# Fri3D_2026_ESP32.net
KiCad netlist of a schematic drawn in Altium Designer
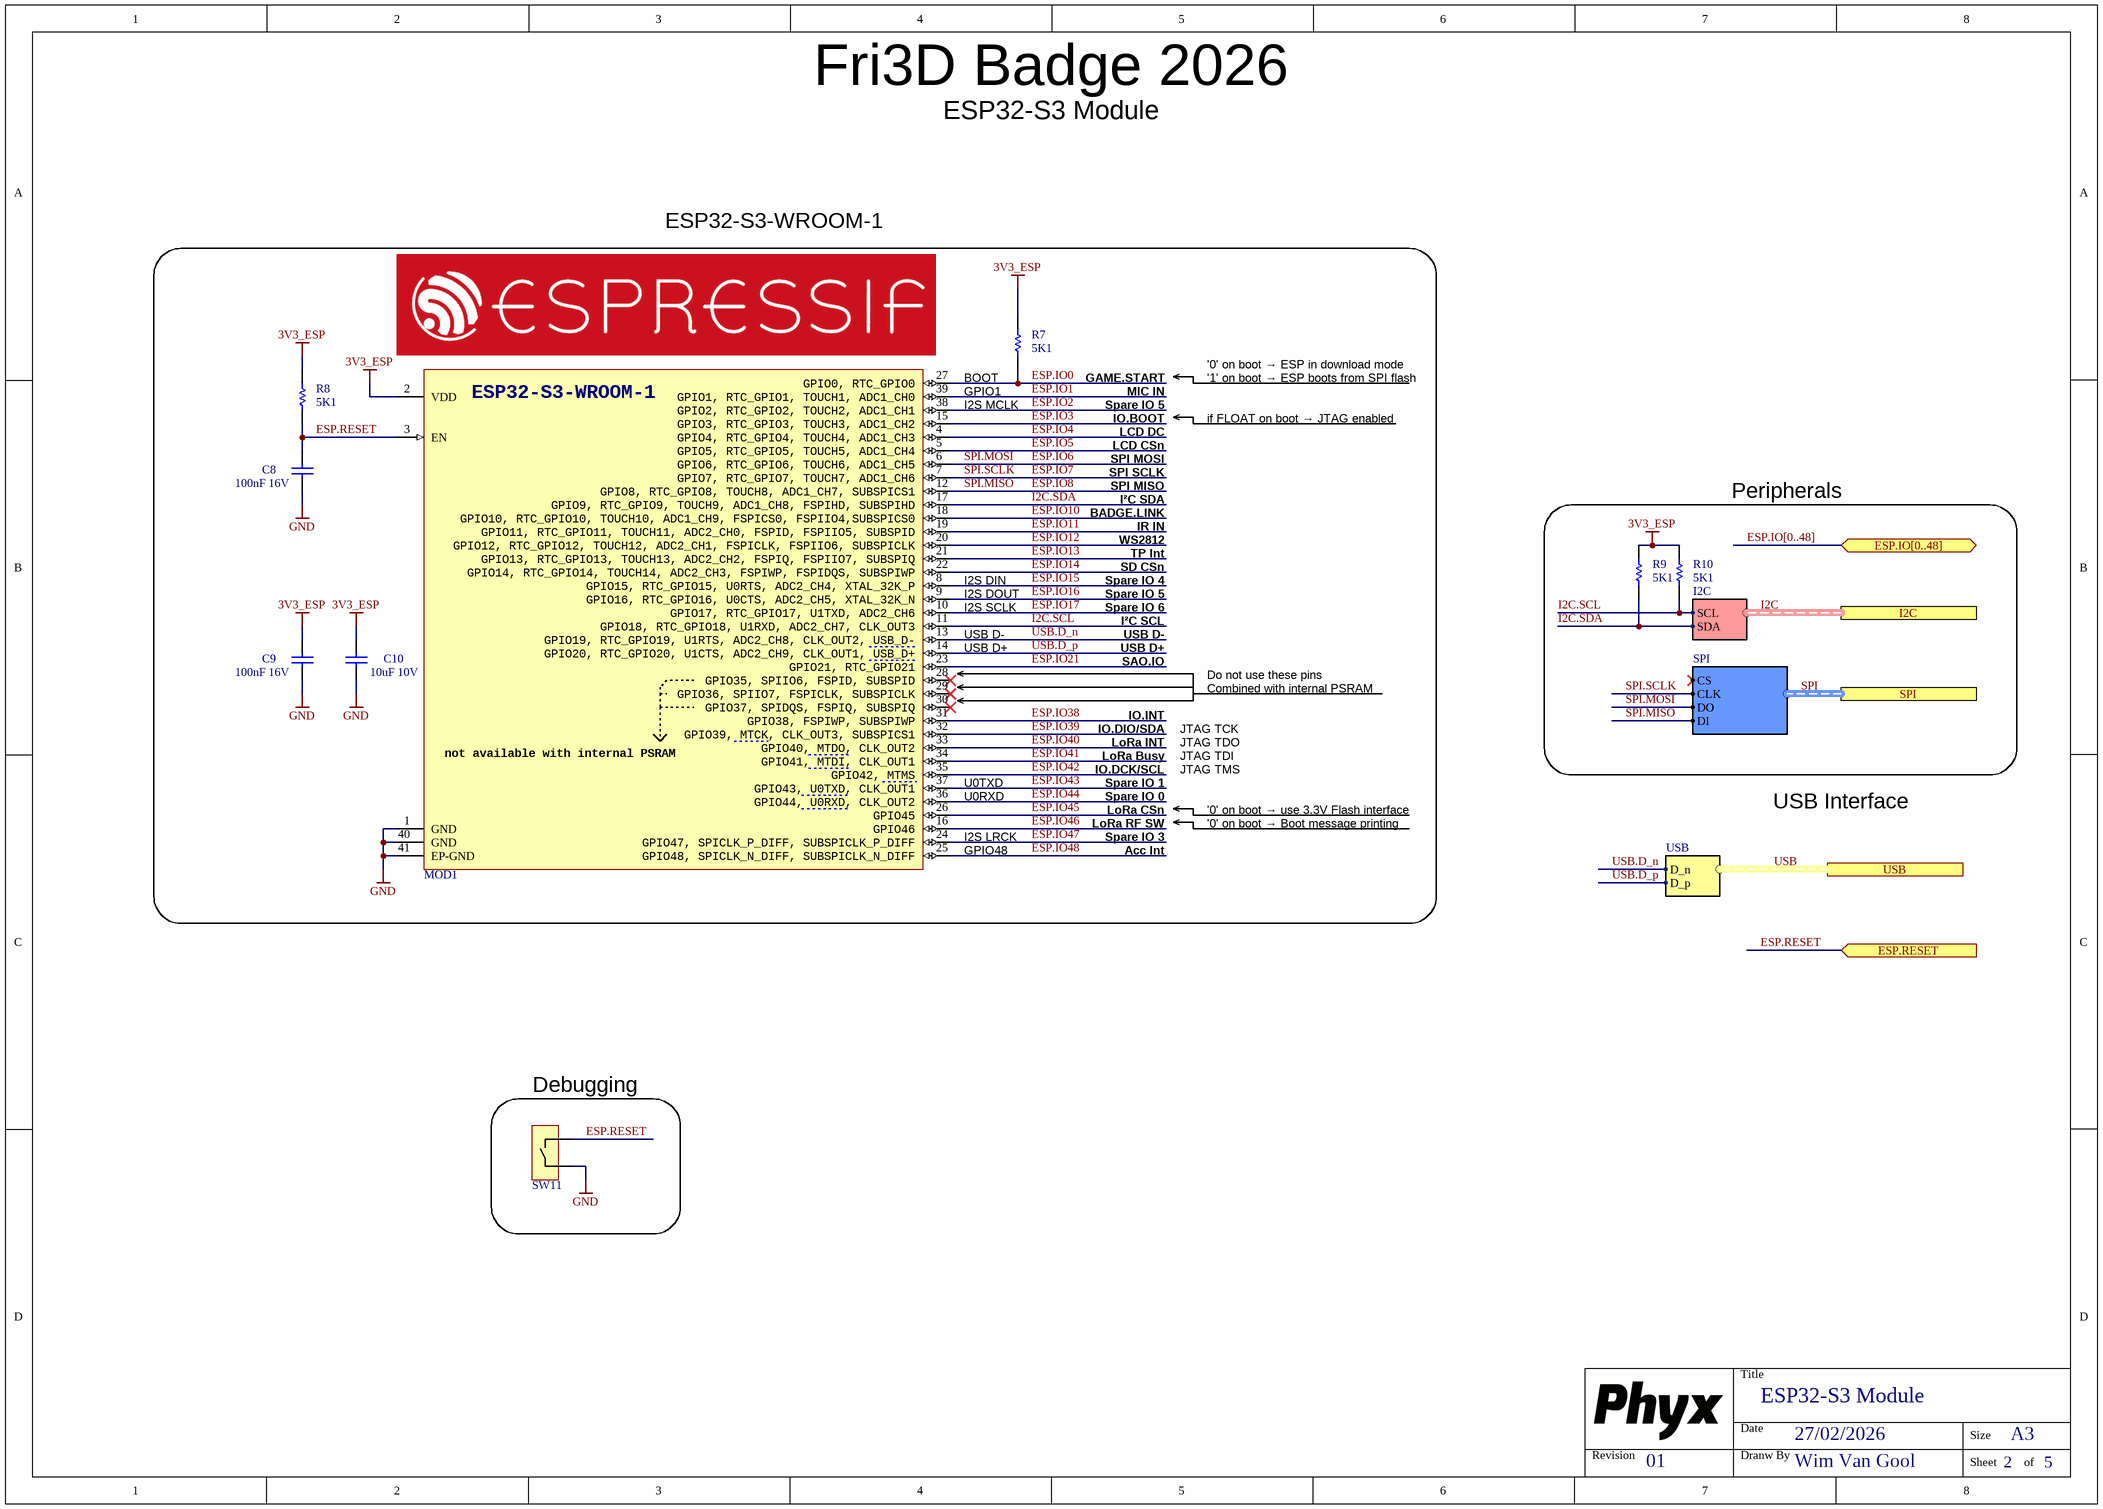
[diagram p0: Fri3D_2026_ESP32.SchDoc]

(export (version "E")
  (design (tool "Eeschema 10.0.6"))
  (components
    (comp (ref "C8")
      (value "100nF 16V")
      (footprint "C0603_N")
      (description "Capacitor Ceramic")
      (libsource (lib "Phyx_Components") (part "CAP_CERAMIC"))
    )
    (comp (ref "C9")
      (value "100nF 16V")
      (footprint "C0603_N")
      (description "Capacitor Ceramic")
      (libsource (lib "Phyx_Components") (part "CAP_CERAMIC"))
    )
    (comp (ref "C10")
      (value "10uF 10V")
      (footprint "C0805_N")
      (description "Capacitor Ceramic")
      (libsource (lib "Phyx_Components") (part "CAP_CERAMIC"))
    )
    (comp (ref "MOD1")
      (value "ESP32-S3 based WROOM-1 16MB Flash, 8MB PSRAM")
      (footprint "ESP-ESP32-S3-WROOM-1")
      (description "WiFi # MOD ESP32-S3-WROOM-1")
      (libsource (lib "Phyx_Components") (part "ESP-ESP32-S3-WROOM-1"))
    )
    (comp (ref "R7")
      (value "5K1")
      (footprint "R0603_N")
      (libsource (lib "Phyx_Components") (part "RESISTOR"))
    )
    (comp (ref "R8")
      (value "5K1")
      (footprint "R0603_N")
      (libsource (lib "Phyx_Components") (part "RESISTOR"))
    )
    (comp (ref "R9")
      (value "5K1")
      (footprint "R0603_N")
      (libsource (lib "Phyx_Components") (part "RESISTOR"))
    )
    (comp (ref "R10")
      (value "5K1")
      (footprint "R0603_N")
      (libsource (lib "Phyx_Components") (part "RESISTOR"))
    )
    (comp (ref "SW11")
      (value "4.5x4.5mm tact SMD H3,8mm")
      (footprint "WE_430181038816")
      (libsource (lib "Phyx_Components") (part "SW_TACT"))
    )
  )
  (nets
    (net (code "24") (name "/ESP.IO0") (class "Default")
      (node (ref "MOD1") (pin "27") (pinfunction "GPIO0,_RTC_GPIO0_27") (pintype "bidirectional"))
      (node (ref "R7") (pin "2") (pinfunction "2_2") (pintype "passive"))
    )
    (net (code "25") (name "/ESP.IO1") (class "Default")
      (node (ref "MOD1") (pin "39") (pinfunction "GPIO1,_RTC_GPIO1,_TOUCH1,_ADC1_CH0_39") (pintype "bidirectional"))
    )
    (net (code "26") (name "/ESP.IO2") (class "Default")
      (node (ref "MOD1") (pin "38") (pinfunction "GPIO2,_RTC_GPIO2,_TOUCH2,_ADC1_CH1_38") (pintype "bidirectional"))
    )
    (net (code "27") (name "/ESP.IO3") (class "Default")
      (node (ref "MOD1") (pin "15") (pinfunction "GPIO3,_RTC_GPIO3,_TOUCH3,_ADC1_CH2_15") (pintype "bidirectional"))
    )
    (net (code "28") (name "/ESP.IO4") (class "Default")
      (node (ref "MOD1") (pin "4") (pinfunction "GPIO4,_RTC_GPIO4,_TOUCH4,_ADC1_CH3_4") (pintype "bidirectional"))
    )
    (net (code "29") (name "/ESP.IO5") (class "Default")
      (node (ref "MOD1") (pin "5") (pinfunction "GPIO5,_RTC_GPIO5,_TOUCH5,_ADC1_CH4_5") (pintype "bidirectional"))
    )
    (net (code "30") (name "/ESP.IO6") (class "Default")
      (node (ref "MOD1") (pin "6") (pinfunction "GPIO6,_RTC_GPIO6,_TOUCH6,_ADC1_CH5_6") (pintype "bidirectional"))
    )
    (net (code "31") (name "/ESP.IO7") (class "Default")
      (node (ref "MOD1") (pin "7") (pinfunction "GPIO7,_RTC_GPIO7,_TOUCH7,_ADC1_CH6_7") (pintype "bidirectional"))
    )
    (net (code "32") (name "/ESP.IO8") (class "Default")
      (node (ref "MOD1") (pin "12") (pinfunction "GPIO8,_RTC_GPIO8,_TOUCH8,_ADC1_CH7,_SUBSPICS1_12") (pintype "bidirectional"))
    )
    (net (code "33") (name "/ESP.IO10") (class "Default")
      (node (ref "MOD1") (pin "18") (pinfunction "GPIO10,_RTC_GPIO10,_TOUCH10,_ADC1_CH9,_FSPICS0,_FSPIIO4,SUBSPICS0_18") (pintype "bidirectional"))
    )
    (net (code "34") (name "/ESP.IO11") (class "Default")
      (node (ref "MOD1") (pin "19") (pinfunction "GPIO11,_RTC_GPIO11,_TOUCH11,_ADC2_CH0,_FSPID,_FSPIIO5,_SUBSPID_19") (pintype "bidirectional"))
    )
    (net (code "35") (name "/ESP.IO12") (class "Default")
      (node (ref "MOD1") (pin "20") (pinfunction "GPIO12,_RTC_GPIO12,_TOUCH12,_ADC2_CH1,_FSPICLK,_FSPIIO6,_SUBSPICLK_20") (pintype "bidirectional"))
    )
    (net (code "36") (name "/ESP.IO13") (class "Default")
      (node (ref "MOD1") (pin "21") (pinfunction "GPIO13,_RTC_GPIO13,_TOUCH13,_ADC2_CH2,_FSPIQ,_FSPIIO7,_SUBSPIQ_21") (pintype "bidirectional"))
    )
    (net (code "37") (name "/ESP.IO14") (class "Default")
      (node (ref "MOD1") (pin "22") (pinfunction "GPIO14,_RTC_GPIO14,_TOUCH14,_ADC2_CH3,_FSPIWP,_FSPIDQS,_SUBSPIWP_22") (pintype "bidirectional"))
    )
    (net (code "38") (name "/ESP.IO15") (class "Default")
      (node (ref "MOD1") (pin "8") (pinfunction "GPIO15,_RTC_GPIO15,_U0RTS,_ADC2_CH4,_XTAL_32K_P_8") (pintype "bidirectional"))
    )
    (net (code "39") (name "/ESP.IO16") (class "Default")
      (node (ref "MOD1") (pin "9") (pinfunction "GPIO16,_RTC_GPIO16,_U0CTS,_ADC2_CH5,_XTAL_32K_N_9") (pintype "bidirectional"))
    )
    (net (code "40") (name "/ESP.IO17") (class "Default")
      (node (ref "MOD1") (pin "10") (pinfunction "GPIO17,_RTC_GPIO17,_U1TXD,_ADC2_CH6_10") (pintype "bidirectional"))
    )
    (net (code "41") (name "/ESP.IO21") (class "Default")
      (node (ref "MOD1") (pin "23") (pinfunction "GPIO21,_RTC_GPIO21_23") (pintype "bidirectional"))
    )
    (net (code "42") (name "/ESP.IO38") (class "Default")
      (node (ref "MOD1") (pin "31") (pinfunction "GPIO38,_FSPIWP,_SUBSPIWP_31") (pintype "bidirectional"))
    )
    (net (code "43") (name "/ESP.IO39") (class "Default")
      (node (ref "MOD1") (pin "32") (pinfunction "GPIO39,_MTCK,_CLK_OUT3,_SUBSPICS1_32") (pintype "bidirectional"))
    )
    (net (code "44") (name "/ESP.IO40") (class "Default")
      (node (ref "MOD1") (pin "33") (pinfunction "GPIO40,_MTDO,_CLK_OUT2_33") (pintype "bidirectional"))
    )
    (net (code "45") (name "/ESP.IO41") (class "Default")
      (node (ref "MOD1") (pin "34") (pinfunction "GPIO41,_MTDI,_CLK_OUT1_34") (pintype "bidirectional"))
    )
    (net (code "46") (name "/ESP.IO42") (class "Default")
      (node (ref "MOD1") (pin "35") (pinfunction "GPIO42,_MTMS_35") (pintype "bidirectional"))
    )
    (net (code "47") (name "/ESP.IO43") (class "Default")
      (node (ref "MOD1") (pin "37") (pinfunction "GPIO43,_U0TXD,_CLK_OUT1_37") (pintype "bidirectional"))
    )
    (net (code "48") (name "/ESP.IO44") (class "Default")
      (node (ref "MOD1") (pin "36") (pinfunction "GPIO44,_U0RXD,_CLK_OUT2_36") (pintype "bidirectional"))
    )
    (net (code "49") (name "/ESP.IO45") (class "Default")
      (node (ref "MOD1") (pin "26") (pinfunction "GPIO45_26") (pintype "bidirectional"))
    )
    (net (code "50") (name "/ESP.IO46") (class "Default")
      (node (ref "MOD1") (pin "16") (pinfunction "GPIO46_16") (pintype "bidirectional"))
    )
    (net (code "51") (name "/ESP.IO47") (class "Default")
      (node (ref "MOD1") (pin "24") (pinfunction "GPIO47,_SPICLK_P_DIFF,_SUBSPICLK_P_DIFF_24") (pintype "bidirectional"))
    )
    (net (code "52") (name "/ESP.IO48") (class "Default")
      (node (ref "MOD1") (pin "25") (pinfunction "GPIO48,_SPICLK_N_DIFF,_SUBSPICLK_N_DIFF_25") (pintype "bidirectional"))
    )
    (net (code "54") (name "/ESP.RESET") (class "Default")
      (node (ref "C8") (pin "1") (pinfunction "1_1") (pintype "passive"))
      (node (ref "MOD1") (pin "3") (pinfunction "EN_3") (pintype "input"))
      (node (ref "R8") (pin "2") (pinfunction "2_2") (pintype "passive"))
      (node (ref "SW11") (pin "1") (pinfunction "1_1") (pintype "passive"))
    )
    (net (code "55") (name "/I2C.SCL") (class "Default")
      (node (ref "MOD1") (pin "11") (pinfunction "GPIO18,_RTC_GPIO18,_U1RXD,_ADC2_CH7,_CLK_OUT3_11") (pintype "bidirectional"))
      (node (ref "R10") (pin "2") (pinfunction "2_2") (pintype "passive"))
    )
    (net (code "56") (name "/I2C.SDA") (class "Default")
      (node (ref "MOD1") (pin "17") (pinfunction "GPIO9,_RTC_GPIO9,_TOUCH9,_ADC1_CH8,_FSPIHD,_SUBSPIHD_17") (pintype "bidirectional"))
      (node (ref "R9") (pin "2") (pinfunction "2_2") (pintype "passive"))
    )
    (net (code "59") (name "/USB.D_n") (class "Default")
      (node (ref "MOD1") (pin "13") (pinfunction "GPIO19,_RTC_GPIO19,_U1RTS,_ADC2_CH8,_CLK_OUT2,_USB_D-_13") (pintype "bidirectional"))
    )
    (net (code "60") (name "/USB.D_p") (class "Default")
      (node (ref "MOD1") (pin "14") (pinfunction "GPIO20,_RTC_GPIO20,_U1CTS,_ADC2_CH9,_CLK_OUT1,_USB_D+_14") (pintype "bidirectional"))
    )
    (net (code "62") (name "3V3_ESP") (class "Default")
      (node (ref "C10") (pin "1") (pinfunction "1_1") (pintype "passive"))
      (node (ref "C9") (pin "1") (pinfunction "1_1") (pintype "passive"))
      (node (ref "MOD1") (pin "2") (pinfunction "VDD_2") (pintype "power_in"))
      (node (ref "R10") (pin "1") (pinfunction "1_1") (pintype "passive"))
      (node (ref "R7") (pin "1") (pinfunction "1_1") (pintype "passive"))
      (node (ref "R8") (pin "1") (pinfunction "1_1") (pintype "passive"))
      (node (ref "R9") (pin "1") (pinfunction "1_1") (pintype "passive"))
    )
    (net (code "63") (name "GND") (class "Default")
      (node (ref "C10") (pin "2") (pinfunction "2_2") (pintype "passive"))
      (node (ref "C8") (pin "2") (pinfunction "2_2") (pintype "passive"))
      (node (ref "C9") (pin "2") (pinfunction "2_2") (pintype "passive"))
      (node (ref "MOD1") (pin "1") (pinfunction "GND_1") (pintype "power_in"))
      (node (ref "MOD1") (pin "40") (pinfunction "GND_40") (pintype "power_in"))
      (node (ref "MOD1") (pin "41") (pinfunction "EP-GND_41") (pintype "power_in"))
      (node (ref "SW11") (pin "2") (pinfunction "2_2") (pintype "passive"))
    )
    (net (code "64") (name "unconnected-(MOD1-GPIO35,_SPIIO6,_FSPID,_SUBSPID-Pad28)") (class "Default")
      (node (ref "MOD1") (pin "28") (pinfunction "GPIO35,_SPIIO6,_FSPID,_SUBSPID_28") (pintype "bidirectional+no_connect"))
    )
    (net (code "65") (name "unconnected-(MOD1-GPIO36,_SPIIO7,_FSPICLK,_SUBSPICLK-Pad29)") (class "Default")
      (node (ref "MOD1") (pin "29") (pinfunction "GPIO36,_SPIIO7,_FSPICLK,_SUBSPICLK_29") (pintype "bidirectional+no_connect"))
    )
    (net (code "66") (name "unconnected-(MOD1-GPIO37,_SPIDQS,_FSPIQ,_SUBSPIQ-Pad30)") (class "Default")
      (node (ref "MOD1") (pin "30") (pinfunction "GPIO37,_SPIDQS,_FSPIQ,_SUBSPIQ_30") (pintype "bidirectional+no_connect"))
    )
  )
)
